# mLRS-rx-E22-G4-v007.net
KiCad netlist of a schematic drawn in EAGLE
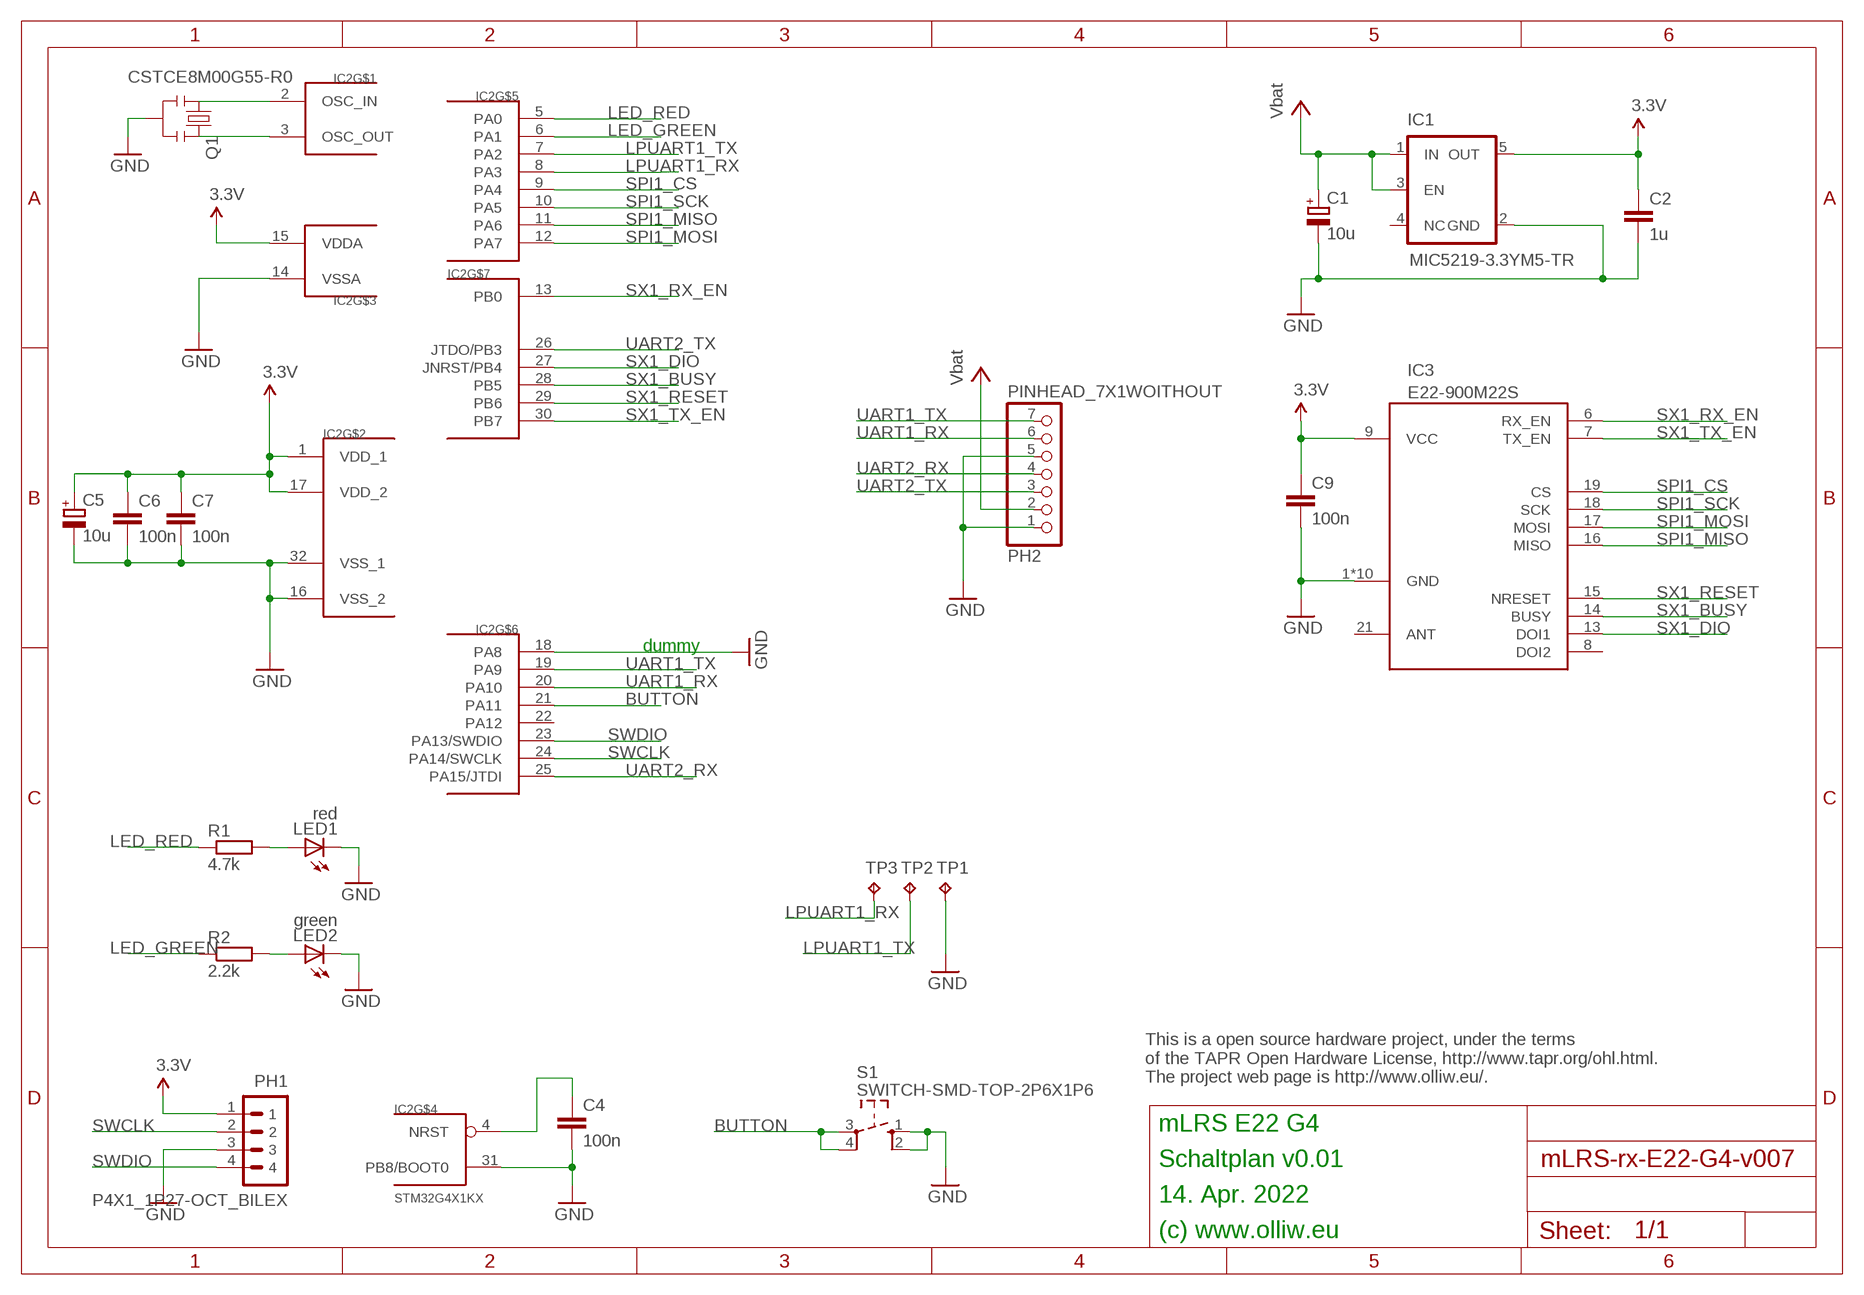
[diagram p0: schematic, sheet 1]

(export (version "E")
  (design (tool "Eeschema 10.0.6"))
  (components
    (comp (ref "C1")
      (value "10u")
      (footprint "eagle-import:SMC_A")
      (libsource (lib "eagle-import") (part "CPOL-EUSMCA"))
    )
    (comp (ref "C2")
      (value "1u")
      (footprint "eagle-import:C0603K")
      (libsource (lib "eagle-import") (part "C-EUC0603K"))
    )
    (comp (ref "C4")
      (value "100n")
      (footprint "eagle-import:C0402")
      (libsource (lib "eagle-import") (part "C-EUC0402"))
    )
    (comp (ref "C5")
      (value "10u")
      (footprint "eagle-import:SMC_A")
      (libsource (lib "eagle-import") (part "CPOL-EUSMCA"))
    )
    (comp (ref "C6")
      (value "100n")
      (footprint "eagle-import:C0402")
      (libsource (lib "eagle-import") (part "C-EUC0402"))
    )
    (comp (ref "C7")
      (value "100n")
      (footprint "eagle-import:C0402")
      (libsource (lib "eagle-import") (part "C-EUC0402"))
    )
    (comp (ref "C9")
      (value "100n")
      (footprint "eagle-import:C0402")
      (libsource (lib "eagle-import") (part "C-EUC0402"))
    )
    (comp (ref "IC1")
      (value "MIC5219-3.3YM5-TR")
      (footprint "eagle-import:SOT23-5")
      (libsource (lib "eagle-import") (part "V_REG_TPS76433SOT23-5"))
    )
    (comp (ref "IC2")
      (value "STM32G4X1KX")
      (footprint "eagle-import:UFQFPN32")
      (libsource (lib "eagle-import") (part "STM32G4X1KX"))
    )
    (comp (ref "IC3")
      (value "E22-900M22S")
      (footprint "eagle-import:E22-900M22S")
      (libsource (lib "eagle-import") (part "E22-900M22S"))
    )
    (comp (ref "LED1")
      (value "red")
      (footprint "eagle-import:CHIPLED_0603")
      (libsource (lib "eagle-import") (part "LEDCHIPLED_0603"))
    )
    (comp (ref "LED2")
      (value "green")
      (footprint "eagle-import:CHIPLED_0603")
      (libsource (lib "eagle-import") (part "LEDCHIPLED_0603"))
    )
    (comp (ref "PH1")
      (value "P4X1_1P27-OCT_BILEX")
      (footprint "eagle-import:4X1_1P27_OCT_BILEX")
      (libsource (lib "eagle-import") (part "P4X1_1P27-OCT_BILEX"))
    )
    (comp (ref "PH2")
      (value "PINHEAD_7X1WOITHOUT")
      (footprint "eagle-import:PINHEAD_7X1_WO")
      (libsource (lib "eagle-import") (part "PINHEAD_7X1WOITHOUT"))
    )
    (comp (ref "Q1")
      (value "CSTCE8M00G55-R0")
      (footprint "eagle-import:RESONATOR-SMD")
      (libsource (lib "eagle-import") (part "RESONATORSMD"))
    )
    (comp (ref "R1")
      (value "4.7k")
      (footprint "eagle-import:R0402")
      (libsource (lib "eagle-import") (part "R-EU_R0402"))
    )
    (comp (ref "R2")
      (value "2.2k")
      (footprint "eagle-import:R0402")
      (libsource (lib "eagle-import") (part "R-EU_R0402"))
    )
    (comp (ref "S1")
      (value "SWITCH-SMD-TOP-2P6X1P6")
      (footprint "eagle-import:TACTILE-SWITCH-SMD-TOP-2P6X1X6")
      (libsource (lib "eagle-import") (part "SWITCH-SMD-TOP-2P6X1P6"))
    )
    (comp (ref "TP1")
      (value "TPB1,27")
      (footprint "eagle-import:B1,27")
      (libsource (lib "eagle-import") (part "TPB1,27"))
    )
    (comp (ref "TP2")
      (value "TPB1,27")
      (footprint "eagle-import:B1,27")
      (libsource (lib "eagle-import") (part "TPB1,27"))
    )
    (comp (ref "TP3")
      (value "TPB1,27")
      (footprint "eagle-import:B1,27")
      (libsource (lib "eagle-import") (part "TPB1,27"))
    )
  )
  (nets
    (net (code "1") (name "/BUTTON") (class "Default")
      (node (ref "IC2") (pin "21") (pinfunction "PA11_21") (pintype "bidirectional"))
      (node (ref "S1") (pin "3") (pinfunction "3_3") (pintype "passive"))
      (node (ref "S1") (pin "4") (pinfunction "4_4") (pintype "passive"))
    )
    (net (code "2") (name "/LED_GREEN") (class "Default")
      (node (ref "IC2") (pin "6") (pinfunction "PA1_6") (pintype "bidirectional"))
      (node (ref "R2") (pin "1") (pinfunction "1_1") (pintype "passive"))
    )
    (net (code "3") (name "/LED_RED") (class "Default")
      (node (ref "IC2") (pin "5") (pinfunction "PA0_5") (pintype "bidirectional"))
      (node (ref "R1") (pin "1") (pinfunction "1_1") (pintype "passive"))
    )
    (net (code "4") (name "/LPUART1_RX") (class "Default")
      (node (ref "IC2") (pin "8") (pinfunction "PA3_8") (pintype "bidirectional"))
      (node (ref "TP3") (pin "TP") (pinfunction "TP_TP") (pintype "input"))
    )
    (net (code "5") (name "/LPUART1_TX") (class "Default")
      (node (ref "IC2") (pin "7") (pinfunction "PA2_7") (pintype "bidirectional"))
      (node (ref "TP2") (pin "TP") (pinfunction "TP_TP") (pintype "input"))
    )
    (net (code "6") (name "/SPI1_CS") (class "Default")
      (node (ref "IC2") (pin "9") (pinfunction "PA4_9") (pintype "bidirectional"))
      (node (ref "IC3") (pin "19") (pinfunction "CS_19") (pintype "bidirectional"))
    )
    (net (code "7") (name "/SPI1_MISO") (class "Default")
      (node (ref "IC2") (pin "11") (pinfunction "PA6_11") (pintype "bidirectional"))
      (node (ref "IC3") (pin "16") (pinfunction "MISO_16") (pintype "bidirectional"))
    )
    (net (code "8") (name "/SPI1_MOSI") (class "Default")
      (node (ref "IC2") (pin "12") (pinfunction "PA7_12") (pintype "bidirectional"))
      (node (ref "IC3") (pin "17") (pinfunction "MOSI_17") (pintype "bidirectional"))
    )
    (net (code "9") (name "/SPI1_SCK") (class "Default")
      (node (ref "IC2") (pin "10") (pinfunction "PA5_10") (pintype "bidirectional"))
      (node (ref "IC3") (pin "18") (pinfunction "SCK_18") (pintype "bidirectional"))
    )
    (net (code "10") (name "/SWCLK") (class "Default")
      (node (ref "IC2") (pin "24") (pinfunction "PA14/SWCLK_24") (pintype "bidirectional"))
      (node (ref "PH1") (pin "2") (pinfunction "2_2") (pintype "passive"))
    )
    (net (code "11") (name "/SWDIO") (class "Default")
      (node (ref "IC2") (pin "23") (pinfunction "PA13/SWDIO_23") (pintype "bidirectional"))
      (node (ref "PH1") (pin "4") (pinfunction "4_4") (pintype "passive"))
    )
    (net (code "12") (name "/SX1_BUSY") (class "Default")
      (node (ref "IC2") (pin "28") (pinfunction "PB5_28") (pintype "bidirectional"))
      (node (ref "IC3") (pin "14") (pinfunction "BUSY_14") (pintype "bidirectional"))
    )
    (net (code "13") (name "/SX1_DIO") (class "Default")
      (node (ref "IC2") (pin "27") (pinfunction "JNRST/PB4_27") (pintype "bidirectional"))
      (node (ref "IC3") (pin "13") (pinfunction "DOI1_13") (pintype "bidirectional"))
    )
    (net (code "14") (name "/SX1_RESET") (class "Default")
      (node (ref "IC2") (pin "29") (pinfunction "PB6_29") (pintype "bidirectional"))
      (node (ref "IC3") (pin "15") (pinfunction "NRESET_15") (pintype "input"))
    )
    (net (code "15") (name "/SX1_RX_EN") (class "Default")
      (node (ref "IC2") (pin "13") (pinfunction "PB0_13") (pintype "bidirectional"))
      (node (ref "IC3") (pin "6") (pinfunction "RX_EN_6") (pintype "bidirectional"))
    )
    (net (code "16") (name "/SX1_TX_EN") (class "Default")
      (node (ref "IC2") (pin "30") (pinfunction "PB7_30") (pintype "bidirectional"))
      (node (ref "IC3") (pin "7") (pinfunction "TX_EN_7") (pintype "bidirectional"))
    )
    (net (code "17") (name "/UART1_RX") (class "Default")
      (node (ref "IC2") (pin "20") (pinfunction "PA10_20") (pintype "bidirectional"))
      (node (ref "PH2") (pin "6") (pinfunction "6_6") (pintype "passive"))
    )
    (net (code "18") (name "/UART1_TX") (class "Default")
      (node (ref "IC2") (pin "19") (pinfunction "PA9_19") (pintype "bidirectional"))
      (node (ref "PH2") (pin "7") (pinfunction "7_7") (pintype "passive"))
    )
    (net (code "19") (name "/UART2_RX") (class "Default")
      (node (ref "IC2") (pin "25") (pinfunction "PA15/JTDI_25") (pintype "bidirectional"))
      (node (ref "PH2") (pin "4") (pinfunction "4_4") (pintype "passive"))
    )
    (net (code "20") (name "/UART2_TX") (class "Default")
      (node (ref "IC2") (pin "26") (pinfunction "JTDO/PB3_26") (pintype "bidirectional"))
      (node (ref "PH2") (pin "3") (pinfunction "3_3") (pintype "passive"))
    )
    (net (code "21") (name "3.3V") (class "Default")
      (node (ref "C2") (pin "1") (pinfunction "1_1") (pintype "passive"))
      (node (ref "C5") (pin "+") (pinfunction "+_+") (pintype "passive"))
      (node (ref "C6") (pin "1") (pinfunction "1_1") (pintype "passive"))
      (node (ref "C7") (pin "1") (pinfunction "1_1") (pintype "passive"))
      (node (ref "C9") (pin "1") (pinfunction "1_1") (pintype "passive"))
      (node (ref "IC1") (pin "5") (pinfunction "OUT_5") (pintype "output"))
      (node (ref "IC2") (pin "1") (pinfunction "VDD_1_1") (pintype "power_in"))
      (node (ref "IC2") (pin "15") (pinfunction "VDDA_15") (pintype "power_in"))
      (node (ref "IC2") (pin "17") (pinfunction "VDD_2_17") (pintype "power_in"))
      (node (ref "IC3") (pin "9") (pinfunction "VCC_9") (pintype "power_in"))
      (node (ref "PH1") (pin "1") (pinfunction "1_1") (pintype "passive"))
    )
    (net (code "22") (name "GND") (class "Default")
      (node (ref "C1") (pin "-") (pinfunction "-_-") (pintype "passive"))
      (node (ref "C2") (pin "2") (pinfunction "2_2") (pintype "passive"))
      (node (ref "C4") (pin "2") (pinfunction "2_2") (pintype "passive"))
      (node (ref "C5") (pin "-") (pinfunction "-_-") (pintype "passive"))
      (node (ref "C6") (pin "2") (pinfunction "2_2") (pintype "passive"))
      (node (ref "C7") (pin "2") (pinfunction "2_2") (pintype "passive"))
      (node (ref "C9") (pin "2") (pinfunction "2_2") (pintype "passive"))
      (node (ref "IC1") (pin "2") (pinfunction "GND_2") (pintype "power_in"))
      (node (ref "IC2") (pin "14") (pinfunction "VSSA_14") (pintype "power_in"))
      (node (ref "IC2") (pin "16") (pinfunction "VSS_2_16") (pintype "power_in"))
      (node (ref "IC2") (pin "18") (pinfunction "PA8_18") (pintype "bidirectional"))
      (node (ref "IC2") (pin "31") (pinfunction "PB8/BOOT0_31") (pintype "input"))
      (node (ref "IC2") (pin "32") (pinfunction "VSS_1_32") (pintype "power_in"))
      (node (ref "IC3") (pin "1") (pinfunction "GND_1") (pintype "power_in"))
      (node (ref "IC3") (pin "10") (pinfunction "GND_10") (pintype "power_in"))
      (node (ref "IC3") (pin "11") (pinfunction "GND_11") (pintype "power_in"))
      (node (ref "IC3") (pin "12") (pinfunction "GND_12") (pintype "power_in"))
      (node (ref "IC3") (pin "2") (pinfunction "GND_2") (pintype "power_in"))
      (node (ref "IC3") (pin "20") (pinfunction "GND_20") (pintype "power_in"))
      (node (ref "IC3") (pin "22") (pinfunction "GND_22") (pintype "power_in"))
      (node (ref "IC3") (pin "3") (pinfunction "GND_3") (pintype "power_in"))
      (node (ref "IC3") (pin "4") (pinfunction "GND_4") (pintype "power_in"))
      (node (ref "IC3") (pin "5") (pinfunction "GND_5") (pintype "power_in"))
      (node (ref "LED1") (pin "C") (pinfunction "C_C") (pintype "passive"))
      (node (ref "LED2") (pin "C") (pinfunction "C_C") (pintype "passive"))
      (node (ref "PH1") (pin "3") (pinfunction "3_3") (pintype "passive"))
      (node (ref "PH2") (pin "1") (pinfunction "1_1") (pintype "passive"))
      (node (ref "PH2") (pin "5") (pinfunction "5_5") (pintype "passive"))
      (node (ref "Q1") (pin "2") (pinfunction "2_2") (pintype "passive"))
      (node (ref "S1") (pin "1") (pinfunction "1_1") (pintype "passive"))
      (node (ref "S1") (pin "2") (pinfunction "2_2") (pintype "passive"))
      (node (ref "TP1") (pin "TP") (pinfunction "TP_TP") (pintype "input"))
    )
    (net (code "23") (name "Net-(IC2A-OSC_IN)") (class "Default")
      (node (ref "IC2") (pin "2") (pinfunction "OSC_IN_2") (pintype "input"))
      (node (ref "Q1") (pin "1") (pinfunction "1_1") (pintype "passive"))
    )
    (net (code "24") (name "Net-(IC2A-OSC_OUT)") (class "Default")
      (node (ref "IC2") (pin "3") (pinfunction "OSC_OUT_3") (pintype "output"))
      (node (ref "Q1") (pin "3") (pinfunction "3_3") (pintype "passive"))
    )
    (net (code "25") (name "Net-(IC2D-NRST)") (class "Default")
      (node (ref "C4") (pin "1") (pinfunction "1_1") (pintype "passive"))
      (node (ref "IC2") (pin "4") (pinfunction "NRST_4") (pintype "input"))
    )
    (net (code "26") (name "Net-(LED1-PadA)") (class "Default")
      (node (ref "LED1") (pin "A") (pinfunction "A_A") (pintype "passive"))
      (node (ref "R1") (pin "2") (pinfunction "2_2") (pintype "passive"))
    )
    (net (code "27") (name "Net-(LED2-PadA)") (class "Default")
      (node (ref "LED2") (pin "A") (pinfunction "A_A") (pintype "passive"))
      (node (ref "R2") (pin "2") (pinfunction "2_2") (pintype "passive"))
    )
    (net (code "28") (name "Vbat") (class "Default")
      (node (ref "C1") (pin "+") (pinfunction "+_+") (pintype "passive"))
      (node (ref "IC1") (pin "1") (pinfunction "IN_1") (pintype "power_in"))
      (node (ref "IC1") (pin "3") (pinfunction "EN_3") (pintype "input"))
      (node (ref "PH2") (pin "2") (pinfunction "2_2") (pintype "passive"))
    )
    (net (code "29") (name "unconnected-(IC1-NC-Pad4)") (class "Default")
      (node (ref "IC1") (pin "4") (pinfunction "NC_4") (pintype "passive"))
    )
    (net (code "30") (name "unconnected-(IC2F-PA12-Pad22)") (class "Default")
      (node (ref "IC2") (pin "22") (pinfunction "PA12_22") (pintype "bidirectional"))
    )
    (net (code "31") (name "unconnected-(IC3-ANT-Pad21)") (class "Default")
      (node (ref "IC3") (pin "21") (pinfunction "ANT_21") (pintype "bidirectional"))
    )
    (net (code "32") (name "unconnected-(IC3-DOI2-Pad8)") (class "Default")
      (node (ref "IC3") (pin "8") (pinfunction "DOI2_8") (pintype "bidirectional"))
    )
  )
)
